# control.net
KiCad netlist of a schematic drawn in Altium Designer
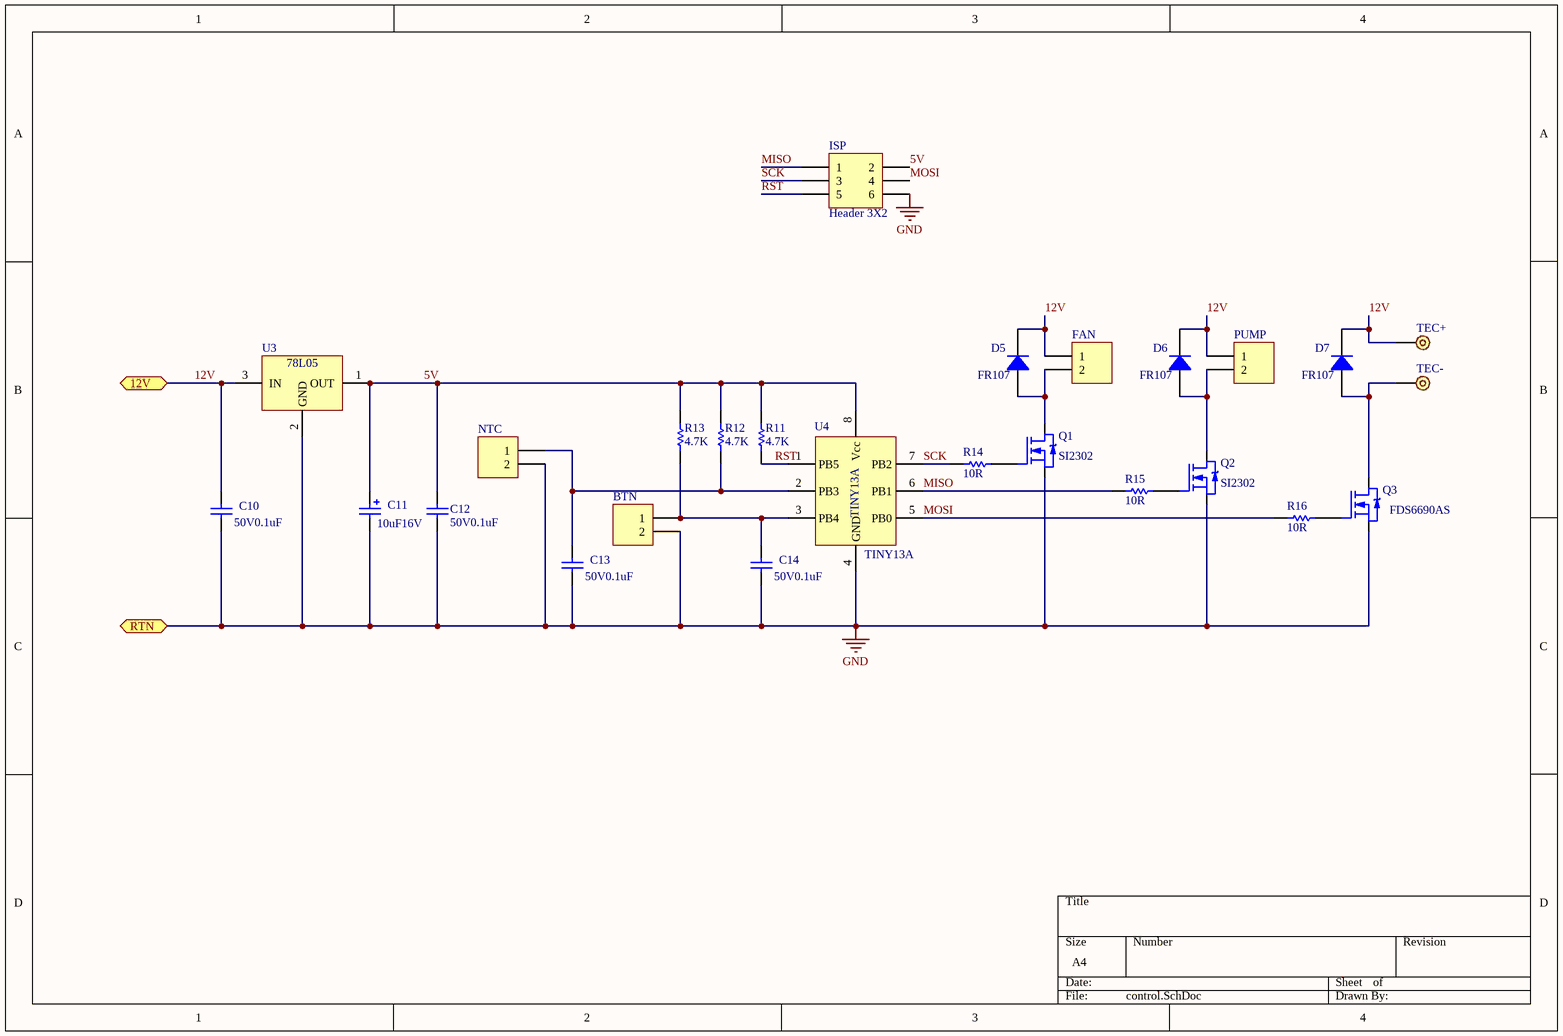
[diagram p0: control.SchDoc]

(export (version "E")
  (design (tool "Eeschema 10.0.6"))
  (components
    (comp (ref "BTN")
      (value "~")
      (footprint "JST2")
      (description "Header, 2-Pin")
      (fields (field (name "PUBLISHER") "Altium Limited"))
      (libsource (lib "") (part "Header 2_1"))
    )
    (comp (ref "C10")
      (value "50V0.1uF")
      (footprint "CAP0805")
      (description "Capacitor")
      (fields (field (name "PUBLISHER") "Altium Limited"))
      (libsource (lib "magcontrol") (part "Cap"))
    )
    (comp (ref "C11")
      (value "10uF16V")
      (footprint "CAP1206")
      (description "Polarized Capacitor (Axial)")
      (fields (field (name "PUBLISHER") "Altium Limited"))
      (libsource (lib "magcontrol") (part "Cap Pol2"))
    )
    (comp (ref "C12")
      (value "50V0.1uF")
      (footprint "CAP0805")
      (description "Capacitor")
      (fields (field (name "PUBLISHER") "Altium Limited"))
      (libsource (lib "magcontrol") (part "Cap"))
    )
    (comp (ref "C13")
      (value "50V0.1uF")
      (footprint "CAP0805")
      (description "Capacitor")
      (fields (field (name "PUBLISHER") "Altium Limited"))
      (libsource (lib "magcontrol") (part "Cap"))
    )
    (comp (ref "C14")
      (value "50V0.1uF")
      (footprint "CAP0805")
      (description "Capacitor")
      (fields (field (name "PUBLISHER") "Altium Limited"))
      (libsource (lib "magcontrol") (part "Cap"))
    )
    (comp (ref "D5")
      (value "FR107")
      (footprint "DO214AC")
      (description "1 Amp Fast Recovery Rectifier")
      (fields (field (name "PUBLISHER") "Altium Limited"))
      (libsource (lib "tecctrl") (part "Diode"))
    )
    (comp (ref "D6")
      (value "FR107")
      (footprint "DO214AC")
      (description "1 Amp Fast Recovery Rectifier")
      (fields (field (name "PUBLISHER") "Altium Limited"))
      (libsource (lib "tecctrl") (part "Diode"))
    )
    (comp (ref "D7")
      (value "FR107")
      (footprint "DO214AC")
      (description "1 Amp Fast Recovery Rectifier")
      (fields (field (name "PUBLISHER") "Altium Limited"))
      (libsource (lib "tecctrl") (part "Diode"))
    )
    (comp (ref "FAN")
      (value "~")
      (footprint "JST2")
      (description "Header, 2-Pin")
      (fields (field (name "PUBLISHER") "Altium Limited"))
      (libsource (lib "Miscellaneous Connectors") (part "Header 2"))
    )
    (comp (ref "ISP")
      (value "Header 3X2")
      (footprint "HDR2X3")
      (description "Header, 3-Pin, Dual row")
      (fields (field (name "PUBLISHER") "Altium Limited"))
      (libsource (lib "Miscellaneous Connectors") (part "Header 3X2"))
    )
    (comp (ref "NTC")
      (value "~")
      (footprint "JST2")
      (description "Header, 2-Pin")
      (fields (field (name "PUBLISHER") "Altium Limited"))
      (libsource (lib "") (part "Header 2_1"))
    )
    (comp (ref "PUMP")
      (value "~")
      (footprint "JST2")
      (description "Header, 2-Pin")
      (fields (field (name "PUBLISHER") "Altium Limited"))
      (libsource (lib "Miscellaneous Connectors") (part "Header 2"))
    )
    (comp (ref "Q1")
      (value "SI2302")
      (footprint "SOT23_NMOS")
      (description "DUAL MOSFET N")
      (fields (field (name "PUBLISHER") "Altium Limited"))
      (libsource (lib "magcontrol") (part "NMOS"))
    )
    (comp (ref "Q2")
      (value "SI2302")
      (footprint "SOT23_NMOS")
      (description "DUAL MOSFET N")
      (fields (field (name "PUBLISHER") "Altium Limited"))
      (libsource (lib "magcontrol") (part "NMOS"))
    )
    (comp (ref "Q3")
      (value "FDS6690AS")
      (footprint "SO8-NMOS")
      (description "DUAL MOSFET N")
      (fields (field (name "PUBLISHER") "Altium Limited"))
      (libsource (lib "magcontrol") (part "NMOS"))
    )
    (comp (ref "R11")
      (value "4.7K")
      (footprint "RES0805")
      (description "Resistor")
      (fields (field (name "PUBLISHER") "Altium Limited"))
      (libsource (lib "magcontrol") (part "Res1"))
    )
    (comp (ref "R12")
      (value "4.7K")
      (footprint "RES0805")
      (description "Resistor")
      (fields (field (name "PUBLISHER") "Altium Limited"))
      (libsource (lib "magcontrol") (part "Res1"))
    )
    (comp (ref "R13")
      (value "4.7K")
      (footprint "RES0805")
      (description "Resistor")
      (fields (field (name "PUBLISHER") "Altium Limited"))
      (libsource (lib "magcontrol") (part "Res1"))
    )
    (comp (ref "R14")
      (value "10R")
      (footprint "RES0805")
      (description "Resistor")
      (fields (field (name "PUBLISHER") "Altium Limited"))
      (libsource (lib "magcontrol") (part "Res1"))
    )
    (comp (ref "R15")
      (value "10R")
      (footprint "RES0805")
      (description "Resistor")
      (fields (field (name "PUBLISHER") "Altium Limited"))
      (libsource (lib "magcontrol") (part "Res1"))
    )
    (comp (ref "R16")
      (value "10R")
      (footprint "RES0805")
      (description "Resistor")
      (fields (field (name "PUBLISHER") "Altium Limited"))
      (libsource (lib "magcontrol") (part "Res1"))
    )
    (comp (ref "TEC+")
      (value "~")
      (footprint "PAD1")
      (description "Header, 1-Pin")
      (fields (field (name "PUBLISHER") "Altium Limited"))
      (libsource (lib "Miscellaneous Connectors") (part "Header1"))
    )
    (comp (ref "TEC-")
      (value "~")
      (footprint "PAD1")
      (description "Header, 1-Pin")
      (fields (field (name "PUBLISHER") "Altium Limited"))
      (libsource (lib "Miscellaneous Connectors") (part "Header1"))
    )
    (comp (ref "U3")
      (value "~")
      (footprint "SOT89_VREG")
      (description "Positive Voltage Regulator")
      (fields (field (name "PUBLISHER") "Altium Limited"))
      (libsource (lib "magcontrol") (part "78L05"))
    )
    (comp (ref "U4")
      (value "TINY13A")
      (footprint "SO8")
      (description "AVR MCU")
      (libsource (lib "magcontrol") (part "TINY13A"))
    )
  )
  (nets
    (net (code "1") (name "/5V") (class "Default")
      (node (ref "C11") (pin "1") (pinfunction "1_1") (pintype "passive"))
      (node (ref "C12") (pin "1") (pinfunction "1_1") (pintype "passive"))
      (node (ref "ISP") (pin "2") (pinfunction "2_2") (pintype "passive"))
      (node (ref "R11") (pin "2") (pinfunction "2_2") (pintype "passive"))
      (node (ref "R12") (pin "2") (pinfunction "2_2") (pintype "passive"))
      (node (ref "R13") (pin "2") (pinfunction "2_2") (pintype "passive"))
      (node (ref "U3") (pin "1") (pinfunction "OUT_1") (pintype "power_in"))
      (node (ref "U4") (pin "8") (pinfunction "Vcc_8") (pintype "power_in"))
    )
    (net (code "2") (name "/12V") (class "Default")
      (node (ref "C10") (pin "1") (pinfunction "1_1") (pintype "passive"))
      (node (ref "D5") (pin "2") (pinfunction "K_2") (pintype "passive"))
      (node (ref "D6") (pin "2") (pinfunction "K_2") (pintype "passive"))
      (node (ref "D7") (pin "2") (pinfunction "K_2") (pintype "passive"))
      (node (ref "FAN") (pin "1") (pinfunction "1_1") (pintype "passive"))
      (node (ref "PUMP") (pin "1") (pinfunction "1_1") (pintype "passive"))
      (node (ref "TEC+") (pin "1") (pinfunction "1_1") (pintype "passive"))
      (node (ref "U3") (pin "3") (pinfunction "IN_3") (pintype "power_in"))
    )
    (net (code "3") (name "/MISO") (class "Default")
      (node (ref "ISP") (pin "1") (pinfunction "1_1") (pintype "passive"))
      (node (ref "R15") (pin "2") (pinfunction "2_2") (pintype "passive"))
      (node (ref "U4") (pin "6") (pinfunction "PB1_6") (pintype "power_in"))
    )
    (net (code "4") (name "/MOSI") (class "Default")
      (node (ref "ISP") (pin "4") (pinfunction "4_4") (pintype "passive"))
      (node (ref "R16") (pin "2") (pinfunction "2_2") (pintype "passive"))
      (node (ref "U4") (pin "5") (pinfunction "PB0_5") (pintype "power_in"))
    )
    (net (code "5") (name "/RST") (class "Default")
      (node (ref "ISP") (pin "5") (pinfunction "5_5") (pintype "passive"))
      (node (ref "R11") (pin "1") (pinfunction "1_1") (pintype "passive"))
      (node (ref "U4") (pin "1") (pinfunction "PB5_1") (pintype "power_in"))
    )
    (net (code "6") (name "/SCK") (class "Default")
      (node (ref "ISP") (pin "3") (pinfunction "3_3") (pintype "passive"))
      (node (ref "R14") (pin "2") (pinfunction "2_2") (pintype "passive"))
      (node (ref "U4") (pin "7") (pinfunction "PB2_7") (pintype "power_in"))
    )
    (net (code "7") (name "GND") (class "Default")
      (node (ref "BTN") (pin "2") (pinfunction "2_2") (pintype "passive"))
      (node (ref "C10") (pin "2") (pinfunction "2_2") (pintype "passive"))
      (node (ref "C11") (pin "2") (pinfunction "2_2") (pintype "passive"))
      (node (ref "C12") (pin "2") (pinfunction "2_2") (pintype "passive"))
      (node (ref "C13") (pin "2") (pinfunction "2_2") (pintype "passive"))
      (node (ref "C14") (pin "2") (pinfunction "2_2") (pintype "passive"))
      (node (ref "ISP") (pin "6") (pinfunction "6_6") (pintype "passive"))
      (node (ref "NTC") (pin "2") (pinfunction "2_2") (pintype "passive"))
      (node (ref "Q1") (pin "S") (pinfunction "S_S") (pintype "passive"))
      (node (ref "Q2") (pin "S") (pinfunction "S_S") (pintype "passive"))
      (node (ref "Q3") (pin "S") (pinfunction "S_S") (pintype "passive"))
      (node (ref "U3") (pin "2") (pinfunction "GND_2") (pintype "power_in"))
      (node (ref "U4") (pin "4") (pinfunction "GND_4") (pintype "power_in"))
    )
    (net (code "8") (name "Net-(D5-A)") (class "Default")
      (node (ref "D5") (pin "1") (pinfunction "A_1") (pintype "passive"))
      (node (ref "FAN") (pin "2") (pinfunction "2_2") (pintype "passive"))
      (node (ref "Q1") (pin "D") (pinfunction "D_D") (pintype "passive"))
    )
    (net (code "9") (name "Net-(D6-A)") (class "Default")
      (node (ref "D6") (pin "1") (pinfunction "A_1") (pintype "passive"))
      (node (ref "PUMP") (pin "2") (pinfunction "2_2") (pintype "passive"))
      (node (ref "Q2") (pin "D") (pinfunction "D_D") (pintype "passive"))
    )
    (net (code "10") (name "Net-(D7-A)") (class "Default")
      (node (ref "D7") (pin "1") (pinfunction "A_1") (pintype "passive"))
      (node (ref "Q3") (pin "D") (pinfunction "D_D") (pintype "passive"))
      (node (ref "TEC-") (pin "1") (pinfunction "1_1") (pintype "passive"))
    )
    (net (code "11") (name "Net-(Q1-PadG)") (class "Default")
      (node (ref "Q1") (pin "G") (pinfunction "G_G") (pintype "passive"))
      (node (ref "R14") (pin "1") (pinfunction "1_1") (pintype "passive"))
    )
    (net (code "12") (name "Net-(Q2-PadG)") (class "Default")
      (node (ref "Q2") (pin "G") (pinfunction "G_G") (pintype "passive"))
      (node (ref "R15") (pin "1") (pinfunction "1_1") (pintype "passive"))
    )
    (net (code "13") (name "Net-(Q3-PadG)") (class "Default")
      (node (ref "Q3") (pin "G") (pinfunction "G_G") (pintype "passive"))
      (node (ref "R16") (pin "1") (pinfunction "1_1") (pintype "passive"))
    )
    (net (code "14") (name "Net-(U4-PB3)") (class "Default")
      (node (ref "C13") (pin "1") (pinfunction "1_1") (pintype "passive"))
      (node (ref "NTC") (pin "1") (pinfunction "1_1") (pintype "passive"))
      (node (ref "R12") (pin "1") (pinfunction "1_1") (pintype "passive"))
      (node (ref "U4") (pin "2") (pinfunction "PB3_2") (pintype "power_in"))
    )
    (net (code "15") (name "Net-(U4-PB4)") (class "Default")
      (node (ref "BTN") (pin "1") (pinfunction "1_1") (pintype "passive"))
      (node (ref "C14") (pin "1") (pinfunction "1_1") (pintype "passive"))
      (node (ref "R13") (pin "1") (pinfunction "1_1") (pintype "passive"))
      (node (ref "U4") (pin "3") (pinfunction "PB4_3") (pintype "power_in"))
    )
  )
)
